# opamp_usrx.net
KiCad netlist of a schematic drawn in EAGLE
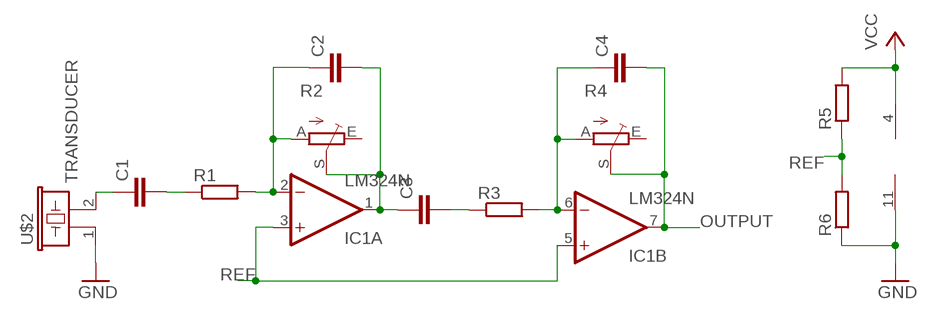
[diagram p0: schematic, sheet 1]

(export (version "E")
  (design (tool "Eeschema 10.0.6"))
  (components
    (comp (ref "C1")
      (value "C-EU025-025X050")
      (footprint "eagle-import:C025-025X050")
      (libsource (lib "eagle-import") (part "C-EU025-025X050"))
    )
    (comp (ref "C2")
      (value "C-EU025-025X050")
      (footprint "eagle-import:C025-025X050")
      (libsource (lib "eagle-import") (part "C-EU025-025X050"))
    )
    (comp (ref "C3")
      (value "C-EU025-025X050")
      (footprint "eagle-import:C025-025X050")
      (libsource (lib "eagle-import") (part "C-EU025-025X050"))
    )
    (comp (ref "C4")
      (value "C-EU025-025X050")
      (footprint "eagle-import:C025-025X050")
      (libsource (lib "eagle-import") (part "C-EU025-025X050"))
    )
    (comp (ref "IC1")
      (value "LM324N")
      (footprint "eagle-import:DIL14")
      (libsource (lib "eagle-import") (part "LM324N"))
    )
    (comp (ref "R1")
      (value "R-EU_0207/2V")
      (footprint "eagle-import:0207_2V")
      (libsource (lib "eagle-import") (part "R-EU_0207/2V"))
    )
    (comp (ref "R2")
      (value "TRIM_EU-S63P")
      (footprint "eagle-import:S63P")
      (libsource (lib "eagle-import") (part "TRIM_EU-S63P"))
    )
    (comp (ref "R3")
      (value "R-EU_0207/2V")
      (footprint "eagle-import:0207_2V")
      (libsource (lib "eagle-import") (part "R-EU_0207/2V"))
    )
    (comp (ref "R4")
      (value "TRIM_EU-S63P")
      (footprint "eagle-import:S63P")
      (libsource (lib "eagle-import") (part "TRIM_EU-S63P"))
    )
    (comp (ref "R5")
      (value "R-EU_0207/2V")
      (footprint "eagle-import:0207_2V")
      (libsource (lib "eagle-import") (part "R-EU_0207/2V"))
    )
    (comp (ref "R6")
      (value "R-EU_0207/2V")
      (footprint "eagle-import:0207_2V")
      (libsource (lib "eagle-import") (part "R-EU_0207/2V"))
    )
    (comp (ref "U$2")
      (value "TRANSDUCER")
      (footprint "eagle-import:TRANSDUCER")
      (libsource (lib "eagle-import") (part "TRANSDUCER"))
    )
  )
  (nets
    (net (code "1") (name "/OUTPUT") (class "Default")
      (node (ref "C4") (pin "2") (pinfunction "2_2") (pintype "passive"))
      (node (ref "IC1") (pin "7") (pinfunction "OUT_7") (pintype "output"))
      (node (ref "R4") (pin "S") (pinfunction "S_S") (pintype "passive"))
    )
    (net (code "2") (name "/REF") (class "Default")
      (node (ref "IC1") (pin "3") (pinfunction "+IN_3") (pintype "input"))
      (node (ref "IC1") (pin "5") (pinfunction "+IN_5") (pintype "input"))
      (node (ref "R5") (pin "1") (pinfunction "1_1") (pintype "passive"))
      (node (ref "R6") (pin "2") (pinfunction "2_2") (pintype "passive"))
    )
    (net (code "3") (name "GND") (class "Default")
      (node (ref "IC1") (pin "11") (pinfunction "V-_11") (pintype "power_in"))
      (node (ref "R6") (pin "1") (pinfunction "1_1") (pintype "passive"))
      (node (ref "U$2") (pin "1") (pinfunction "1_1") (pintype "passive"))
    )
    (net (code "4") (name "Net-(C1-Pad1)") (class "Default")
      (node (ref "C1") (pin "1") (pinfunction "1_1") (pintype "passive"))
      (node (ref "U$2") (pin "2") (pinfunction "2_2") (pintype "passive"))
    )
    (net (code "5") (name "Net-(C1-Pad2)") (class "Default")
      (node (ref "C1") (pin "2") (pinfunction "2_2") (pintype "passive"))
      (node (ref "R1") (pin "1") (pinfunction "1_1") (pintype "passive"))
    )
    (net (code "6") (name "Net-(C3-Pad2)") (class "Default")
      (node (ref "C3") (pin "2") (pinfunction "2_2") (pintype "passive"))
      (node (ref "R3") (pin "1") (pinfunction "1_1") (pintype "passive"))
    )
    (net (code "7") (name "Net-(IC1A--IN)") (class "Default")
      (node (ref "C2") (pin "1") (pinfunction "1_1") (pintype "passive"))
      (node (ref "IC1") (pin "2") (pinfunction "-IN_2") (pintype "input"))
      (node (ref "R1") (pin "2") (pinfunction "2_2") (pintype "passive"))
      (node (ref "R2") (pin "A") (pinfunction "A_A") (pintype "passive"))
    )
    (net (code "8") (name "Net-(IC1A-OUT)") (class "Default")
      (node (ref "C2") (pin "2") (pinfunction "2_2") (pintype "passive"))
      (node (ref "C3") (pin "1") (pinfunction "1_1") (pintype "passive"))
      (node (ref "IC1") (pin "1") (pinfunction "OUT_1") (pintype "output"))
      (node (ref "R2") (pin "S") (pinfunction "S_S") (pintype "passive"))
    )
    (net (code "9") (name "Net-(IC1B--IN)") (class "Default")
      (node (ref "C4") (pin "1") (pinfunction "1_1") (pintype "passive"))
      (node (ref "IC1") (pin "6") (pinfunction "-IN_6") (pintype "input"))
      (node (ref "R3") (pin "2") (pinfunction "2_2") (pintype "passive"))
      (node (ref "R4") (pin "A") (pinfunction "A_A") (pintype "passive"))
    )
    (net (code "10") (name "VCC") (class "Default")
      (node (ref "IC1") (pin "4") (pinfunction "V+_4") (pintype "power_in"))
      (node (ref "R5") (pin "2") (pinfunction "2_2") (pintype "passive"))
    )
    (net (code "11") (name "unconnected-(R2-PadE)") (class "Default")
      (node (ref "R2") (pin "E") (pinfunction "E_E") (pintype "passive"))
    )
    (net (code "12") (name "unconnected-(R4-PadE)") (class "Default")
      (node (ref "R4") (pin "E") (pinfunction "E_E") (pintype "passive"))
    )
  )
)
